# joysticks_left.net
KiCad netlist of a schematic drawn in EAGLE
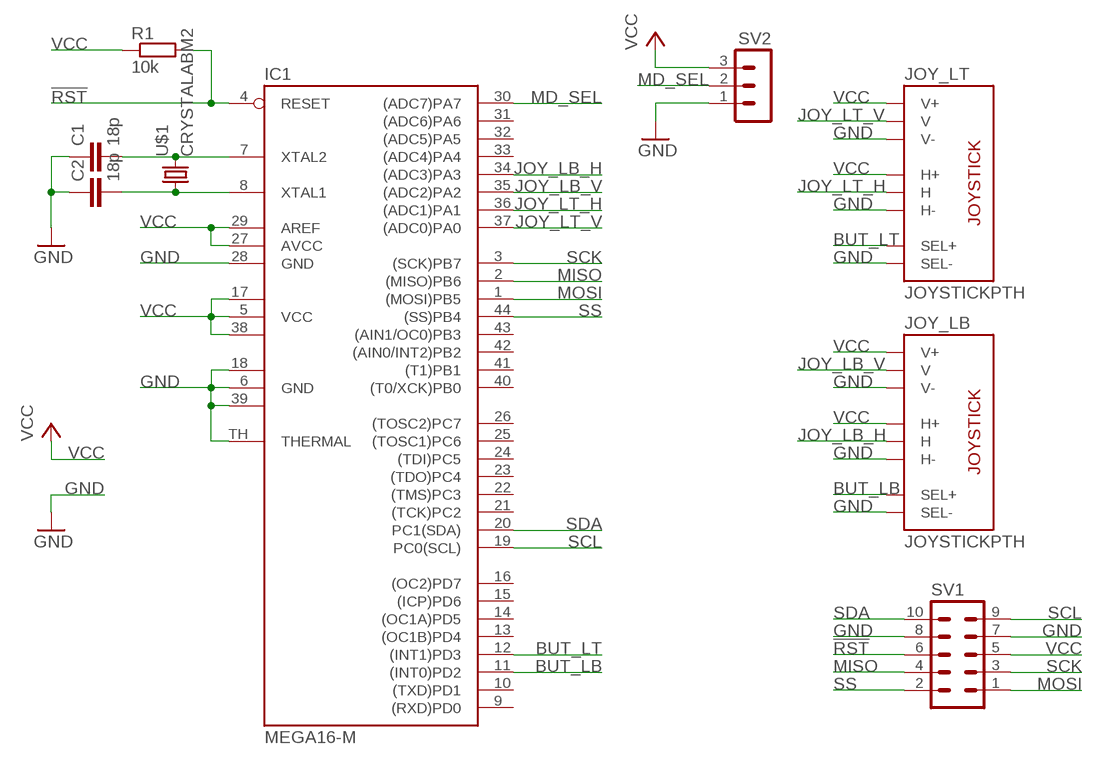
[diagram p0: schematic, sheet 1]

(export (version "E")
  (design (tool "Eeschema 10.0.6"))
  (components
    (comp (ref "C1")
      (value "18p")
      (footprint "eagle-import:C0603")
      (libsource (lib "eagle-import") (part "C-EUC0603"))
    )
    (comp (ref "C2")
      (value "18p")
      (footprint "eagle-import:C0603")
      (libsource (lib "eagle-import") (part "C-EUC0603"))
    )
    (comp (ref "IC1")
      (value "MEGA16-M")
      (footprint "eagle-import:MLF44-TH")
      (fields (field (name "MPN") "ATMEGA16-16MU"))
      (libsource (lib "eagle-import") (part "MEGA16-M"))
    )
    (comp (ref "JOY_LB")
      (value "JOYSTICKPTH")
      (footprint "eagle-import:JOYSTICK")
      (libsource (lib "eagle-import") (part "JOYSTICKPTH"))
    )
    (comp (ref "JOY_LT")
      (value "JOYSTICKPTH")
      (footprint "eagle-import:JOYSTICK")
      (libsource (lib "eagle-import") (part "JOYSTICKPTH"))
    )
    (comp (ref "R1")
      (value "10k")
      (footprint "eagle-import:R0603")
      (libsource (lib "eagle-import") (part "R-EU_R0603"))
    )
    (comp (ref "SV1")
      (value "MA05-2")
      (footprint "eagle-import:MA05-2")
      (libsource (lib "eagle-import") (part "MA05-2"))
    )
    (comp (ref "SV2")
      (value "MA03-1")
      (footprint "eagle-import:MA03-1")
      (libsource (lib "eagle-import") (part "MA03-1"))
    )
    (comp (ref "U$1")
      (value "CRYSTALABM2")
      (footprint "eagle-import:ABM2")
      (libsource (lib "eagle-import") (part "CRYSTALABM2"))
    )
  )
  (nets
    (net (code "1") (name "/BUT_LB") (class "Default")
      (node (ref "IC1") (pin "11") (pinfunction "(INT0)PD2_11") (pintype "bidirectional"))
      (node (ref "JOY_LB") (pin "B1A") (pinfunction "SEL+_B1A") (pintype "bidirectional"))
    )
    (net (code "2") (name "/BUT_LT") (class "Default")
      (node (ref "IC1") (pin "12") (pinfunction "(INT1)PD3_12") (pintype "bidirectional"))
      (node (ref "JOY_LT") (pin "B1A") (pinfunction "SEL+_B1A") (pintype "bidirectional"))
    )
    (net (code "3") (name "/JOY_LB_H") (class "Default")
      (node (ref "IC1") (pin "34") (pinfunction "(ADC3)PA3_34") (pintype "bidirectional"))
      (node (ref "JOY_LB") (pin "H2") (pinfunction "H_H2") (pintype "bidirectional"))
    )
    (net (code "4") (name "/JOY_LB_V") (class "Default")
      (node (ref "IC1") (pin "35") (pinfunction "(ADC2)PA2_35") (pintype "bidirectional"))
      (node (ref "JOY_LB") (pin "V2") (pinfunction "V_V2") (pintype "bidirectional"))
    )
    (net (code "5") (name "/JOY_LT_H") (class "Default")
      (node (ref "IC1") (pin "36") (pinfunction "(ADC1)PA1_36") (pintype "bidirectional"))
      (node (ref "JOY_LT") (pin "H2") (pinfunction "H_H2") (pintype "bidirectional"))
    )
    (net (code "6") (name "/JOY_LT_V") (class "Default")
      (node (ref "IC1") (pin "37") (pinfunction "(ADC0)PA0_37") (pintype "bidirectional"))
      (node (ref "JOY_LT") (pin "V2") (pinfunction "V_V2") (pintype "bidirectional"))
    )
    (net (code "7") (name "/MD_SEL") (class "Default")
      (node (ref "IC1") (pin "30") (pinfunction "(ADC7)PA7_30") (pintype "bidirectional"))
      (node (ref "SV2") (pin "2") (pinfunction "2_2") (pintype "passive"))
    )
    (net (code "8") (name "/MISO") (class "Default")
      (node (ref "IC1") (pin "2") (pinfunction "(MISO)PB6_2") (pintype "bidirectional"))
      (node (ref "SV1") (pin "4") (pinfunction "4_4") (pintype "passive"))
    )
    (net (code "9") (name "/MOSI") (class "Default")
      (node (ref "IC1") (pin "1") (pinfunction "(MOSI)PB5_1") (pintype "bidirectional"))
      (node (ref "SV1") (pin "1") (pinfunction "1_1") (pintype "passive"))
    )
    (net (code "10") (name "/SCK") (class "Default")
      (node (ref "IC1") (pin "3") (pinfunction "(SCK)PB7_3") (pintype "bidirectional"))
      (node (ref "SV1") (pin "3") (pinfunction "3_3") (pintype "passive"))
    )
    (net (code "11") (name "/SCL") (class "Default")
      (node (ref "IC1") (pin "19") (pinfunction "PC0(SCL)_19") (pintype "bidirectional"))
      (node (ref "SV1") (pin "9") (pinfunction "9_9") (pintype "passive"))
    )
    (net (code "12") (name "/SDA") (class "Default")
      (node (ref "IC1") (pin "20") (pinfunction "PC1(SDA)_20") (pintype "bidirectional"))
      (node (ref "SV1") (pin "10") (pinfunction "10_10") (pintype "passive"))
    )
    (net (code "13") (name "/SS") (class "Default")
      (node (ref "IC1") (pin "44") (pinfunction "(SS)PB4_44") (pintype "bidirectional"))
      (node (ref "SV1") (pin "2") (pinfunction "2_2") (pintype "passive"))
    )
    (net (code "14") (name "/~{RST}") (class "Default")
      (node (ref "IC1") (pin "4") (pinfunction "RESET_4") (pintype "input"))
      (node (ref "R1") (pin "2") (pinfunction "2_2") (pintype "passive"))
      (node (ref "SV1") (pin "6") (pinfunction "6_6") (pintype "passive"))
    )
    (net (code "15") (name "GND") (class "Default")
      (node (ref "C1") (pin "1") (pinfunction "1_1") (pintype "passive"))
      (node (ref "C2") (pin "1") (pinfunction "1_1") (pintype "passive"))
      (node (ref "IC1") (pin "18") (pinfunction "GND1_18") (pintype "power_in"))
      (node (ref "IC1") (pin "28") (pinfunction "GND_28") (pintype "power_in"))
      (node (ref "IC1") (pin "39") (pinfunction "GND2_39") (pintype "power_in"))
      (node (ref "IC1") (pin "6") (pinfunction "GND_6") (pintype "power_in"))
      (node (ref "IC1") (pin "TH") (pinfunction "THERMAL_TH") (pintype "input"))
      (node (ref "JOY_LB") (pin "B2A") (pinfunction "SEL-_B2A") (pintype "bidirectional"))
      (node (ref "JOY_LB") (pin "H3") (pinfunction "H-_H3") (pintype "bidirectional"))
      (node (ref "JOY_LB") (pin "V3") (pinfunction "V-_V3") (pintype "bidirectional"))
      (node (ref "JOY_LT") (pin "B2A") (pinfunction "SEL-_B2A") (pintype "bidirectional"))
      (node (ref "JOY_LT") (pin "H3") (pinfunction "H-_H3") (pintype "bidirectional"))
      (node (ref "JOY_LT") (pin "V3") (pinfunction "V-_V3") (pintype "bidirectional"))
      (node (ref "SV1") (pin "7") (pinfunction "7_7") (pintype "passive"))
      (node (ref "SV1") (pin "8") (pinfunction "8_8") (pintype "passive"))
      (node (ref "SV2") (pin "1") (pinfunction "1_1") (pintype "passive"))
    )
    (net (code "16") (name "Net-(IC1-XTAL1)") (class "Default")
      (node (ref "C2") (pin "2") (pinfunction "2_2") (pintype "passive"))
      (node (ref "IC1") (pin "8") (pinfunction "XTAL1_8") (pintype "bidirectional"))
      (node (ref "U$1") (pin "P$1") (pinfunction "1_P$1") (pintype "passive"))
    )
    (net (code "17") (name "Net-(IC1-XTAL2)") (class "Default")
      (node (ref "C1") (pin "2") (pinfunction "2_2") (pintype "passive"))
      (node (ref "IC1") (pin "7") (pinfunction "XTAL2_7") (pintype "bidirectional"))
      (node (ref "U$1") (pin "P$2") (pinfunction "2_P$2") (pintype "passive"))
    )
    (net (code "18") (name "VCC") (class "Default")
      (node (ref "IC1") (pin "17") (pinfunction "VCC1_17") (pintype "power_in"))
      (node (ref "IC1") (pin "27") (pinfunction "AVCC_27") (pintype "power_in"))
      (node (ref "IC1") (pin "29") (pinfunction "AREF_29") (pintype "passive"))
      (node (ref "IC1") (pin "38") (pinfunction "VCC2_38") (pintype "power_in"))
      (node (ref "IC1") (pin "5") (pinfunction "VCC_5") (pintype "power_in"))
      (node (ref "JOY_LB") (pin "H1") (pinfunction "H+_H1") (pintype "bidirectional"))
      (node (ref "JOY_LB") (pin "V1") (pinfunction "V+_V1") (pintype "bidirectional"))
      (node (ref "JOY_LT") (pin "H1") (pinfunction "H+_H1") (pintype "bidirectional"))
      (node (ref "JOY_LT") (pin "V1") (pinfunction "V+_V1") (pintype "bidirectional"))
      (node (ref "R1") (pin "1") (pinfunction "1_1") (pintype "passive"))
      (node (ref "SV1") (pin "5") (pinfunction "5_5") (pintype "passive"))
      (node (ref "SV2") (pin "3") (pinfunction "3_3") (pintype "passive"))
    )
    (net (code "19") (name "unconnected-(IC1-(ADC4)PA4-Pad33)") (class "Default")
      (node (ref "IC1") (pin "33") (pinfunction "(ADC4)PA4_33") (pintype "bidirectional"))
    )
    (net (code "20") (name "unconnected-(IC1-(ADC5)PA5-Pad32)") (class "Default")
      (node (ref "IC1") (pin "32") (pinfunction "(ADC5)PA5_32") (pintype "bidirectional"))
    )
    (net (code "21") (name "unconnected-(IC1-(ADC6)PA6-Pad31)") (class "Default")
      (node (ref "IC1") (pin "31") (pinfunction "(ADC6)PA6_31") (pintype "bidirectional"))
    )
    (net (code "22") (name "unconnected-(IC1-(AIN0{slash}INT2)PB2-Pad42)") (class "Default")
      (node (ref "IC1") (pin "42") (pinfunction "(AIN0/INT2)PB2_42") (pintype "bidirectional"))
    )
    (net (code "23") (name "unconnected-(IC1-(AIN1{slash}OC0)PB3-Pad43)") (class "Default")
      (node (ref "IC1") (pin "43") (pinfunction "(AIN1/OC0)PB3_43") (pintype "bidirectional"))
    )
    (net (code "24") (name "unconnected-(IC1-(ICP)PD6-Pad15)") (class "Default")
      (node (ref "IC1") (pin "15") (pinfunction "(ICP)PD6_15") (pintype "bidirectional"))
    )
    (net (code "25") (name "unconnected-(IC1-(OC1A)PD5-Pad14)") (class "Default")
      (node (ref "IC1") (pin "14") (pinfunction "(OC1A)PD5_14") (pintype "bidirectional"))
    )
    (net (code "26") (name "unconnected-(IC1-(OC1B)PD4-Pad13)") (class "Default")
      (node (ref "IC1") (pin "13") (pinfunction "(OC1B)PD4_13") (pintype "bidirectional"))
    )
    (net (code "27") (name "unconnected-(IC1-(OC2)PD7-Pad16)") (class "Default")
      (node (ref "IC1") (pin "16") (pinfunction "(OC2)PD7_16") (pintype "bidirectional"))
    )
    (net (code "28") (name "unconnected-(IC1-(RXD)PD0-Pad9)") (class "Default")
      (node (ref "IC1") (pin "9") (pinfunction "(RXD)PD0_9") (pintype "bidirectional"))
    )
    (net (code "29") (name "unconnected-(IC1-(T0{slash}XCK)PB0-Pad40)") (class "Default")
      (node (ref "IC1") (pin "40") (pinfunction "(T0/XCK)PB0_40") (pintype "bidirectional"))
    )
    (net (code "30") (name "unconnected-(IC1-(T1)PB1-Pad41)") (class "Default")
      (node (ref "IC1") (pin "41") (pinfunction "(T1)PB1_41") (pintype "bidirectional"))
    )
    (net (code "31") (name "unconnected-(IC1-(TCK)PC2-Pad21)") (class "Default")
      (node (ref "IC1") (pin "21") (pinfunction "(TCK)PC2_21") (pintype "bidirectional"))
    )
    (net (code "32") (name "unconnected-(IC1-(TDI)PC5-Pad24)") (class "Default")
      (node (ref "IC1") (pin "24") (pinfunction "(TDI)PC5_24") (pintype "bidirectional"))
    )
    (net (code "33") (name "unconnected-(IC1-(TDO)PC4-Pad23)") (class "Default")
      (node (ref "IC1") (pin "23") (pinfunction "(TDO)PC4_23") (pintype "bidirectional"))
    )
    (net (code "34") (name "unconnected-(IC1-(TMS)PC3-Pad22)") (class "Default")
      (node (ref "IC1") (pin "22") (pinfunction "(TMS)PC3_22") (pintype "bidirectional"))
    )
    (net (code "35") (name "unconnected-(IC1-(TOSC1)PC6-Pad25)") (class "Default")
      (node (ref "IC1") (pin "25") (pinfunction "(TOSC1)PC6_25") (pintype "bidirectional"))
    )
    (net (code "36") (name "unconnected-(IC1-(TOSC2)PC7-Pad26)") (class "Default")
      (node (ref "IC1") (pin "26") (pinfunction "(TOSC2)PC7_26") (pintype "bidirectional"))
    )
    (net (code "37") (name "unconnected-(IC1-(TXD)PD1-Pad10)") (class "Default")
      (node (ref "IC1") (pin "10") (pinfunction "(TXD)PD1_10") (pintype "bidirectional"))
    )
  )
)
